# batterieChargeur.net
KiCad netlist of a schematic drawn in EAGLE
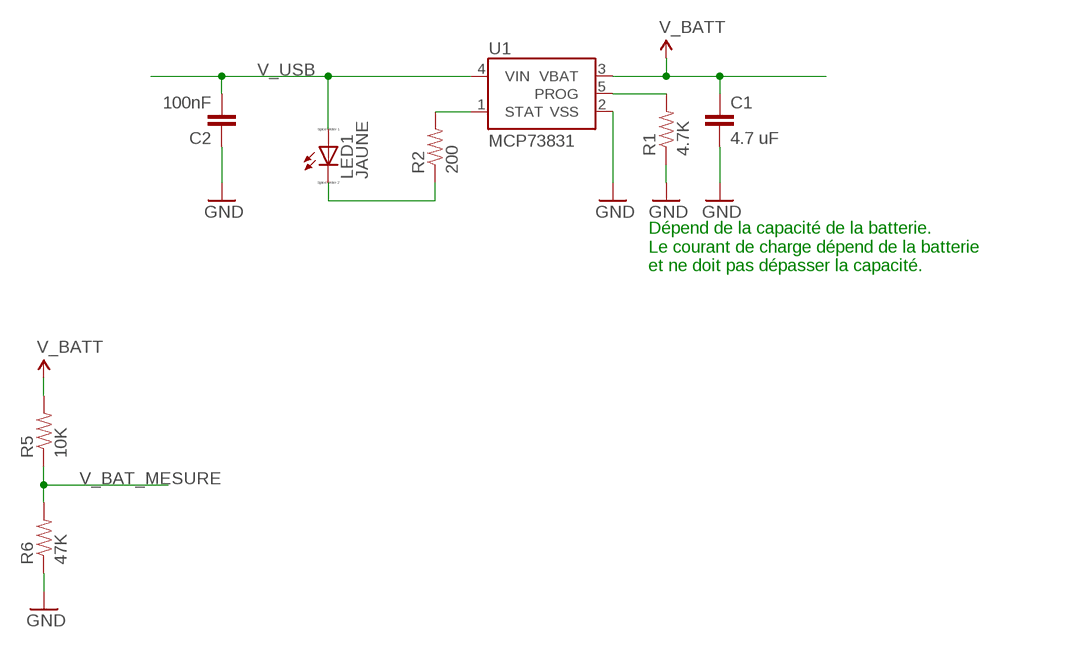
[diagram p0: schematic, sheet 1]

(export (version "E")
  (design (tool "Eeschema 10.0.6"))
  (components
    (comp (ref "C1")
      (value "4.7 uF")
      (footprint "eagle-import:0805")
      (libsource (lib "eagle-import") (part "CAP0805"))
    )
    (comp (ref "C2")
      (value "100nF")
      (footprint "eagle-import:0805")
      (libsource (lib "eagle-import") (part "SparkFun-Passives_CAP0805"))
    )
    (comp (ref "LED1")
      (value "JAUNE")
      (footprint "eagle-import:LED_1206")
      (libsource (lib "eagle-import") (part "LED_E"))
    )
    (comp (ref "R1")
      (value "4.7K")
      (footprint "eagle-import:0805")
      (libsource (lib "eagle-import") (part "RESISTOR0805-RES"))
    )
    (comp (ref "R2")
      (value "200")
      (footprint "eagle-import:0805")
      (libsource (lib "eagle-import") (part "RESISTOR0805-RES"))
    )
    (comp (ref "R5")
      (value "10K")
      (footprint "eagle-import:0805")
      (libsource (lib "eagle-import") (part "RESISTOR0805-RES"))
    )
    (comp (ref "R6")
      (value "47K")
      (footprint "eagle-import:0805")
      (libsource (lib "eagle-import") (part "RESISTOR0805-RES"))
    )
    (comp (ref "U1")
      (value "MCP73831")
      (footprint "eagle-import:SOT23-5")
      (libsource (lib "eagle-import") (part "MCP73831"))
    )
  )
  (nets
    (net (code "1") (name "/V_BAT_MESURE") (class "Default")
      (node (ref "R5") (pin "1") (pinfunction "1_1") (pintype "passive"))
      (node (ref "R6") (pin "2") (pinfunction "2_2") (pintype "passive"))
    )
    (net (code "2") (name "/V_USB") (class "Default")
      (node (ref "C2") (pin "2") (pinfunction "2_2") (pintype "passive"))
      (node (ref "LED1") (pin "A") (pinfunction "A_A") (pintype "passive"))
      (node (ref "U1") (pin "4") (pinfunction "VIN_4") (pintype "power_in"))
    )
    (net (code "3") (name "GND") (class "Default")
      (node (ref "C1") (pin "2") (pinfunction "2_2") (pintype "passive"))
      (node (ref "C2") (pin "1") (pinfunction "1_1") (pintype "passive"))
      (node (ref "R1") (pin "1") (pinfunction "1_1") (pintype "passive"))
      (node (ref "R6") (pin "1") (pinfunction "1_1") (pintype "passive"))
      (node (ref "U1") (pin "2") (pinfunction "VSS_2") (pintype "power_in"))
    )
    (net (code "4") (name "Net-(LED1-PadC)") (class "Default")
      (node (ref "LED1") (pin "C") (pinfunction "C_C") (pintype "passive"))
      (node (ref "R2") (pin "1") (pinfunction "1_1") (pintype "passive"))
    )
    (net (code "5") (name "Net-(U1-PROG)") (class "Default")
      (node (ref "R1") (pin "2") (pinfunction "2_2") (pintype "passive"))
      (node (ref "U1") (pin "5") (pinfunction "PROG_5") (pintype "input"))
    )
    (net (code "6") (name "Net-(U1-STAT)") (class "Default")
      (node (ref "R2") (pin "2") (pinfunction "2_2") (pintype "passive"))
      (node (ref "U1") (pin "1") (pinfunction "STAT_1") (pintype "output"))
    )
    (net (code "7") (name "V_BATT") (class "Default")
      (node (ref "C1") (pin "1") (pinfunction "1_1") (pintype "passive"))
      (node (ref "R5") (pin "2") (pinfunction "2_2") (pintype "passive"))
      (node (ref "U1") (pin "3") (pinfunction "VBAT_3") (pintype "power_in"))
    )
  )
)
